# Arduino-Pro-Mini.net
KiCad netlist of a schematic drawn in EAGLE
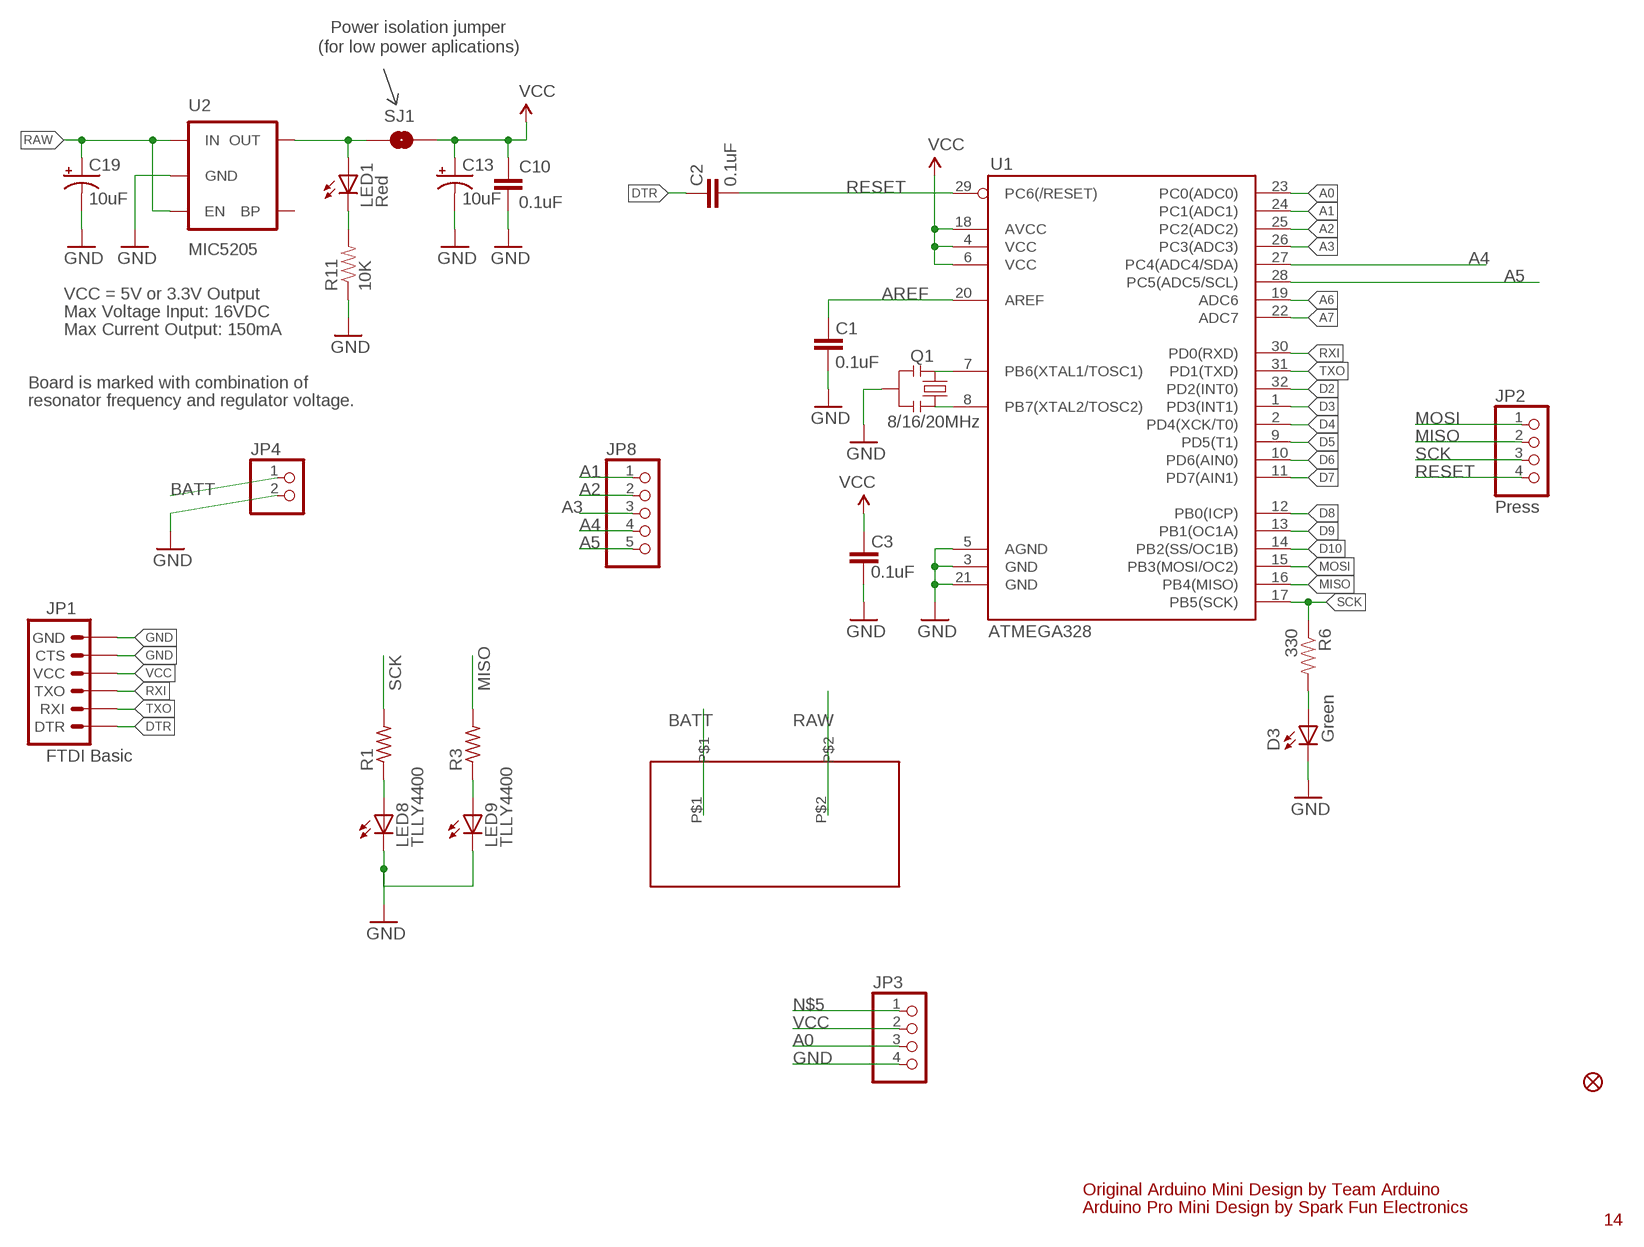
[diagram p0: schematic, sheet 1]

(export (version "E")
  (design (tool "Eeschema 10.0.6"))
  (components
    (comp (ref "C1")
      (value "0.1uF")
      (footprint "eagle-import:0603-CAP")
      (libsource (lib "eagle-import") (part "CAP0603-CAP"))
    )
    (comp (ref "C2")
      (value "0.1uF")
      (footprint "eagle-import:0603-CAP")
      (libsource (lib "eagle-import") (part "CAP0603-CAP"))
    )
    (comp (ref "C3")
      (value "0.1uF")
      (footprint "eagle-import:0603-CAP")
      (libsource (lib "eagle-import") (part "CAP0603-CAP"))
    )
    (comp (ref "C10")
      (value "0.1uF")
      (footprint "eagle-import:0603-CAP")
      (libsource (lib "eagle-import") (part "CAP0603-CAP"))
    )
    (comp (ref "C13")
      (value "10uF")
      (footprint "eagle-import:EIA3216")
      (libsource (lib "eagle-import") (part "CAP_POL1206"))
    )
    (comp (ref "C19")
      (value "10uF")
      (footprint "eagle-import:EIA3216")
      (libsource (lib "eagle-import") (part "CAP_POL1206"))
    )
    (comp (ref "D3")
      (value "Green")
      (footprint "eagle-import:0603-LED-ALT1")
      (libsource (lib "eagle-import") (part "LED"))
    )
    (comp (ref "JP1")
      (value "FTDI Basic")
      (footprint "eagle-import:1X06")
      (libsource (lib "eagle-import") (part "ARDUINO_SERIAL_PROGRAMPTH"))
    )
    (comp (ref "JP2")
      (value "Press")
      (footprint "eagle-import:1X04")
      (libsource (lib "eagle-import") (part "PINHD-1X4"))
    )
    (comp (ref "JP3")
      (value "PINHD-1X4")
      (footprint "eagle-import:1X04")
      (libsource (lib "eagle-import") (part "PINHD-1X4"))
    )
    (comp (ref "JP4")
      (value "PINHD-1X2")
      (footprint "eagle-import:1X02")
      (libsource (lib "eagle-import") (part "PINHD-1X2"))
    )
    (comp (ref "JP5")
      (value "FIDUCIALUFIDUCIAL")
      (footprint "eagle-import:MICRO-FIDUCIAL")
      (libsource (lib "eagle-import") (part "FIDUCIALUFIDUCIAL"))
    )
    (comp (ref "JP8")
      (value "PINHD-1X5")
      (footprint "eagle-import:1X05")
      (libsource (lib "eagle-import") (part "PINHD-1X5"))
    )
    (comp (ref "LED1")
      (value "Red")
      (footprint "eagle-import:0603-LED-ALT1")
      (libsource (lib "eagle-import") (part "LED"))
    )
    (comp (ref "LED8")
      (value "TLLY4400")
      (footprint "eagle-import:LED3MM")
      (fields (field (name "MF") "VISHAY SEMICONDUCTOR"))
      (libsource (lib "eagle-import") (part "TLLY4400"))
    )
    (comp (ref "LED9")
      (value "TLLY4400")
      (footprint "eagle-import:LED3MM")
      (fields (field (name "MF") "VISHAY SEMICONDUCTOR"))
      (libsource (lib "eagle-import") (part "TLLY4400"))
    )
    (comp (ref "Q1")
      (value "8/16/20MHz")
      (footprint "eagle-import:RESONATOR-SMD-1_1")
      (libsource (lib "eagle-import") (part "RESONATOR1{colon}1"))
    )
    (comp (ref "R1")
      (value "R-US_R0603")
      (footprint "eagle-import:R0603")
      (libsource (lib "eagle-import") (part "R-US_R0603"))
    )
    (comp (ref "R3")
      (value "R-US_R0603")
      (footprint "eagle-import:R0603")
      (libsource (lib "eagle-import") (part "R-US_R0603"))
    )
    (comp (ref "R6")
      (value "330")
      (footprint "eagle-import:0603-RES")
      (libsource (lib "eagle-import") (part "RESISTOR0603-RES"))
    )
    (comp (ref "R11")
      (value "10K")
      (footprint "eagle-import:0603-RES")
      (libsource (lib "eagle-import") (part "RESISTOR0603-RES"))
    )
    (comp (ref "SJ1")
      (value "SOLDERJUMPERNC")
      (footprint "eagle-import:SJ_2S")
      (libsource (lib "eagle-import") (part "SOLDERJUMPERNC"))
    )
    (comp (ref "U$1")
      (value "SWITCH-DW182")
      (footprint "eagle-import:SWITCH-CW182")
      (libsource (lib "eagle-import") (part "SWITCH-DW182"))
    )
    (comp (ref "U1")
      (value "ATMEGA328")
      (footprint "eagle-import:TQFP32-08")
      (libsource (lib "eagle-import") (part "ATMEGA168"))
    )
    (comp (ref "U2")
      (value "MIC5205")
      (footprint "eagle-import:SOT23-5")
      (libsource (lib "eagle-import") (part "V_REG_LDOSMD"))
    )
  )
  (nets
    (net (code "1") (name "/A4") (class "Default")
      (node (ref "JP8") (pin "4") (pinfunction "4_4") (pintype "passive"))
      (node (ref "U1") (pin "27") (pinfunction "PC4(ADC4/SDA)_27") (pintype "bidirectional"))
    )
    (net (code "2") (name "/A5") (class "Default")
      (node (ref "JP8") (pin "5") (pinfunction "5_5") (pintype "passive"))
      (node (ref "U1") (pin "28") (pinfunction "PC5(ADC5/SCL)_28") (pintype "bidirectional"))
    )
    (net (code "3") (name "/AREF") (class "Default")
      (node (ref "C1") (pin "2") (pinfunction "2_2") (pintype "passive"))
      (node (ref "U1") (pin "20") (pinfunction "AREF_20") (pintype "bidirectional"))
    )
    (net (code "4") (name "/BATT") (class "Default")
      (node (ref "JP4") (pin "1") (pinfunction "1_1") (pintype "passive"))
      (node (ref "U$1") (pin "P$1") (pinfunction "P$1_P$1") (pintype "bidirectional"))
    )
    (net (code "5") (name "/N$5") (class "Default")
      (node (ref "JP3") (pin "1") (pinfunction "1_1") (pintype "passive"))
    )
    (net (code "6") (name "/RESET") (class "Default")
      (node (ref "C2") (pin "1") (pinfunction "1_1") (pintype "passive"))
      (node (ref "JP2") (pin "4") (pinfunction "4_4") (pintype "passive"))
      (node (ref "U1") (pin "29") (pinfunction "PC6(/RESET)_29") (pintype "bidirectional"))
    )
    (net (code "7") (name "A0") (class "Default")
      (node (ref "JP3") (pin "3") (pinfunction "3_3") (pintype "passive"))
      (node (ref "U1") (pin "23") (pinfunction "PC0(ADC0)_23") (pintype "bidirectional"))
    )
    (net (code "8") (name "A1") (class "Default")
      (node (ref "JP8") (pin "1") (pinfunction "1_1") (pintype "passive"))
      (node (ref "U1") (pin "24") (pinfunction "PC1(ADC1)_24") (pintype "bidirectional"))
    )
    (net (code "9") (name "A2") (class "Default")
      (node (ref "JP8") (pin "2") (pinfunction "2_2") (pintype "passive"))
      (node (ref "U1") (pin "25") (pinfunction "PC2(ADC2)_25") (pintype "bidirectional"))
    )
    (net (code "10") (name "A3") (class "Default")
      (node (ref "JP8") (pin "3") (pinfunction "3_3") (pintype "passive"))
      (node (ref "U1") (pin "26") (pinfunction "PC3(ADC3)_26") (pintype "bidirectional"))
    )
    (net (code "11") (name "A6") (class "Default")
      (node (ref "U1") (pin "19") (pinfunction "ADC6_19") (pintype "bidirectional"))
    )
    (net (code "12") (name "A7") (class "Default")
      (node (ref "U1") (pin "22") (pinfunction "ADC7_22") (pintype "bidirectional"))
    )
    (net (code "13") (name "D2") (class "Default")
      (node (ref "U1") (pin "32") (pinfunction "PD2(INT0)_32") (pintype "bidirectional"))
    )
    (net (code "14") (name "D3") (class "Default")
      (node (ref "U1") (pin "1") (pinfunction "PD3(INT1)_1") (pintype "bidirectional"))
    )
    (net (code "15") (name "D4") (class "Default")
      (node (ref "U1") (pin "2") (pinfunction "PD4(XCK/T0)_2") (pintype "bidirectional"))
    )
    (net (code "16") (name "D5") (class "Default")
      (node (ref "U1") (pin "9") (pinfunction "PD5(T1)_9") (pintype "bidirectional"))
    )
    (net (code "17") (name "D6") (class "Default")
      (node (ref "U1") (pin "10") (pinfunction "PD6(AIN0)_10") (pintype "bidirectional"))
    )
    (net (code "18") (name "D7") (class "Default")
      (node (ref "U1") (pin "11") (pinfunction "PD7(AIN1)_11") (pintype "bidirectional"))
    )
    (net (code "19") (name "D8") (class "Default")
      (node (ref "U1") (pin "12") (pinfunction "PB0(ICP)_12") (pintype "bidirectional"))
    )
    (net (code "20") (name "D9") (class "Default")
      (node (ref "U1") (pin "13") (pinfunction "PB1(OC1A)_13") (pintype "bidirectional"))
    )
    (net (code "21") (name "D10") (class "Default")
      (node (ref "U1") (pin "14") (pinfunction "PB2(SS/OC1B)_14") (pintype "bidirectional"))
    )
    (net (code "22") (name "DTR") (class "Default")
      (node (ref "C2") (pin "2") (pinfunction "2_2") (pintype "passive"))
      (node (ref "JP1") (pin "1") (pinfunction "DTR_1") (pintype "passive"))
    )
    (net (code "23") (name "GND") (class "Default")
      (node (ref "C1") (pin "1") (pinfunction "1_1") (pintype "passive"))
      (node (ref "C10") (pin "2") (pinfunction "2_2") (pintype "passive"))
      (node (ref "C13") (pin "C") (pinfunction "-_C") (pintype "passive"))
      (node (ref "C19") (pin "C") (pinfunction "-_C") (pintype "passive"))
      (node (ref "C3") (pin "1") (pinfunction "1_1") (pintype "passive"))
      (node (ref "D3") (pin "C") (pinfunction "C_C") (pintype "passive"))
      (node (ref "JP1") (pin "5") (pinfunction "CTS_5") (pintype "passive"))
      (node (ref "JP1") (pin "6") (pinfunction "GND_6") (pintype "passive"))
      (node (ref "JP3") (pin "4") (pinfunction "4_4") (pintype "passive"))
      (node (ref "JP4") (pin "2") (pinfunction "2_2") (pintype "passive"))
      (node (ref "LED8") (pin "K") (pinfunction "C_K") (pintype "passive"))
      (node (ref "LED9") (pin "K") (pinfunction "C_K") (pintype "passive"))
      (node (ref "Q1") (pin "2") (pinfunction "2_2") (pintype "passive"))
      (node (ref "R11") (pin "1") (pinfunction "1_1") (pintype "passive"))
      (node (ref "U1") (pin "21") (pinfunction "GND_21") (pintype "bidirectional"))
      (node (ref "U1") (pin "3") (pinfunction "GND_3") (pintype "bidirectional"))
      (node (ref "U1") (pin "5") (pinfunction "AGND_5") (pintype "bidirectional"))
      (node (ref "U2") (pin "2") (pinfunction "GND_2") (pintype "input"))
    )
    (net (code "24") (name "MISO") (class "Default")
      (node (ref "JP2") (pin "2") (pinfunction "2_2") (pintype "passive"))
      (node (ref "R3") (pin "2") (pinfunction "2_2") (pintype "passive"))
      (node (ref "U1") (pin "16") (pinfunction "PB4(MISO)_16") (pintype "bidirectional"))
    )
    (net (code "25") (name "MOSI") (class "Default")
      (node (ref "JP2") (pin "1") (pinfunction "1_1") (pintype "passive"))
      (node (ref "U1") (pin "15") (pinfunction "PB3(MOSI/OC2)_15") (pintype "bidirectional"))
    )
    (net (code "26") (name "Net-(D3-PadA)") (class "Default")
      (node (ref "D3") (pin "A") (pinfunction "A_A") (pintype "passive"))
      (node (ref "R6") (pin "2") (pinfunction "2_2") (pintype "passive"))
    )
    (net (code "27") (name "Net-(LED1-PadC)") (class "Default")
      (node (ref "LED1") (pin "C") (pinfunction "C_C") (pintype "passive"))
      (node (ref "R11") (pin "2") (pinfunction "2_2") (pintype "passive"))
    )
    (net (code "28") (name "Net-(LED8-PadA)") (class "Default")
      (node (ref "LED8") (pin "A") (pinfunction "A_A") (pintype "passive"))
      (node (ref "R1") (pin "1") (pinfunction "1_1") (pintype "passive"))
    )
    (net (code "29") (name "Net-(LED9-PadA)") (class "Default")
      (node (ref "LED9") (pin "A") (pinfunction "A_A") (pintype "passive"))
      (node (ref "R3") (pin "1") (pinfunction "1_1") (pintype "passive"))
    )
    (net (code "30") (name "Net-(U1-PB6(XTAL1{slash}TOSC1))") (class "Default")
      (node (ref "Q1") (pin "1") (pinfunction "1_1") (pintype "passive"))
      (node (ref "U1") (pin "7") (pinfunction "PB6(XTAL1/TOSC1)_7") (pintype "bidirectional"))
    )
    (net (code "31") (name "Net-(U1-PB7(XTAL2{slash}TOSC2))") (class "Default")
      (node (ref "Q1") (pin "3") (pinfunction "3_3") (pintype "passive"))
      (node (ref "U1") (pin "8") (pinfunction "PB7(XTAL2/TOSC2)_8") (pintype "bidirectional"))
    )
    (net (code "32") (name "Net-(U2-OUT)") (class "Default")
      (node (ref "LED1") (pin "A") (pinfunction "A_A") (pintype "passive"))
      (node (ref "SJ1") (pin "1") (pinfunction "1_1") (pintype "passive"))
      (node (ref "U2") (pin "5") (pinfunction "OUT_5") (pintype "passive"))
    )
    (net (code "33") (name "RAW") (class "Default")
      (node (ref "C19") (pin "A") (pinfunction "+_A") (pintype "passive"))
      (node (ref "U$1") (pin "P$2") (pinfunction "P$2_P$2") (pintype "bidirectional"))
      (node (ref "U2") (pin "1") (pinfunction "IN_1") (pintype "input"))
      (node (ref "U2") (pin "3") (pinfunction "EN_3") (pintype "input"))
    )
    (net (code "34") (name "RXI") (class "Default")
      (node (ref "JP1") (pin "3") (pinfunction "TXO_3") (pintype "passive"))
      (node (ref "U1") (pin "30") (pinfunction "PD0(RXD)_30") (pintype "bidirectional"))
    )
    (net (code "35") (name "SCK") (class "Default")
      (node (ref "JP2") (pin "3") (pinfunction "3_3") (pintype "passive"))
      (node (ref "R1") (pin "2") (pinfunction "2_2") (pintype "passive"))
      (node (ref "R6") (pin "1") (pinfunction "1_1") (pintype "passive"))
      (node (ref "U1") (pin "17") (pinfunction "PB5(SCK)_17") (pintype "bidirectional"))
    )
    (net (code "36") (name "TXO") (class "Default")
      (node (ref "JP1") (pin "2") (pinfunction "RXI_2") (pintype "passive"))
      (node (ref "U1") (pin "31") (pinfunction "PD1(TXD)_31") (pintype "bidirectional"))
    )
    (net (code "37") (name "VCC") (class "Default")
      (node (ref "C10") (pin "1") (pinfunction "1_1") (pintype "passive"))
      (node (ref "C13") (pin "A") (pinfunction "+_A") (pintype "passive"))
      (node (ref "C3") (pin "2") (pinfunction "2_2") (pintype "passive"))
      (node (ref "JP1") (pin "4") (pinfunction "VCC_4") (pintype "passive"))
      (node (ref "JP3") (pin "2") (pinfunction "2_2") (pintype "passive"))
      (node (ref "SJ1") (pin "2") (pinfunction "2_2") (pintype "passive"))
      (node (ref "U1") (pin "18") (pinfunction "AVCC_18") (pintype "bidirectional"))
      (node (ref "U1") (pin "4") (pinfunction "VCC_4") (pintype "bidirectional"))
      (node (ref "U1") (pin "6") (pinfunction "VCC_6") (pintype "bidirectional"))
    )
    (net (code "38") (name "unconnected-(U2-BP-Pad4)") (class "Default")
      (node (ref "U2") (pin "4") (pinfunction "BP_4") (pintype "input"))
    )
  )
)
